# design.net
KiCad netlist of a schematic drawn in Altium Designer
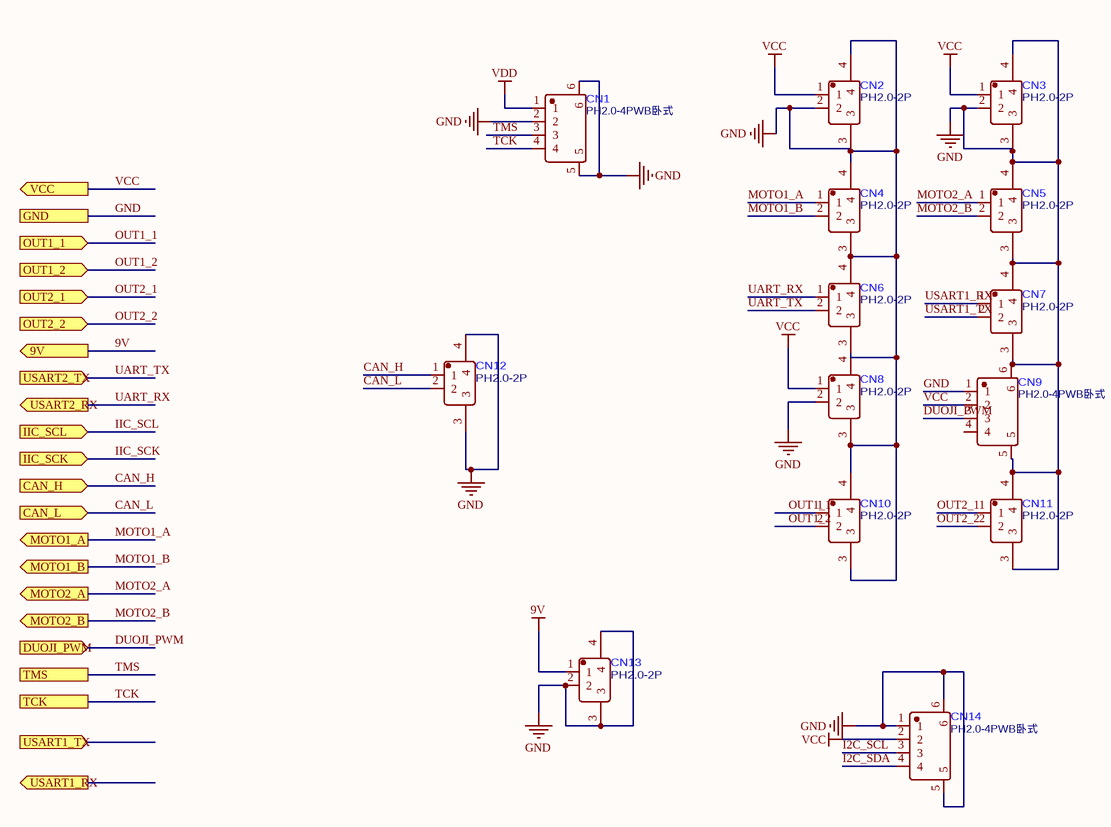
[diagram p0: 外围接口.SchDoc]

(export (version "E")
  (design (tool "Eeschema 10.0.6"))
  (components
    (comp (ref "CN1")
      (value "PH2.0-4PWB卧式")
      (footprint "CONN-SMD_PH2.0-4PWB")
      (libsource (lib "PH2.0-4PWB卧式_2021-08-21") (part "PH2.0-4PWB卧式"))
    )
    (comp (ref "CN2")
      (value "PH2.0-2P")
      (footprint "CONN-SMD_PH2.0-1X2PW")
      (libsource (lib "PH2.0-2P_2021-08-20") (part "PH2.0-2P"))
    )
    (comp (ref "CN3")
      (value "PH2.0-2P")
      (footprint "CONN-SMD_PH2.0-1X2PW")
      (libsource (lib "PH2.0-2P_2021-08-20") (part "PH2.0-2P"))
    )
    (comp (ref "CN4")
      (value "PH2.0-2P")
      (footprint "CONN-SMD_PH2.0-1X2PW")
      (libsource (lib "PH2.0-2P_2021-08-20") (part "PH2.0-2P"))
    )
    (comp (ref "CN5")
      (value "PH2.0-2P")
      (footprint "CONN-SMD_PH2.0-1X2PW")
      (libsource (lib "PH2.0-2P_2021-08-20") (part "PH2.0-2P"))
    )
    (comp (ref "CN6")
      (value "PH2.0-2P")
      (footprint "CONN-SMD_PH2.0-1X2PW")
      (libsource (lib "PH2.0-2P_2021-08-20") (part "PH2.0-2P"))
    )
    (comp (ref "CN7")
      (value "PH2.0-2P")
      (footprint "CONN-SMD_PH2.0-1X2PW")
      (libsource (lib "PH2.0-2P_2021-08-20") (part "PH2.0-2P"))
    )
    (comp (ref "CN8")
      (value "PH2.0-2P")
      (footprint "CONN-SMD_PH2.0-1X2PW")
      (libsource (lib "PH2.0-2P_2021-08-20") (part "PH2.0-2P"))
    )
    (comp (ref "CN9")
      (value "PH2.0-4PWB卧式")
      (footprint "CONN-SMD_PH2.0-4PWB")
      (libsource (lib "PH2.0-4PWB卧式_2021-08-21") (part "PH2.0-4PWB卧式"))
    )
    (comp (ref "CN10")
      (value "PH2.0-2P")
      (footprint "CONN-SMD_PH2.0-1X2PW")
      (libsource (lib "PH2.0-2P_2021-08-20") (part "PH2.0-2P"))
    )
    (comp (ref "CN11")
      (value "PH2.0-2P")
      (footprint "CONN-SMD_PH2.0-1X2PW")
      (libsource (lib "PH2.0-2P_2021-08-20") (part "PH2.0-2P"))
    )
    (comp (ref "CN12")
      (value "PH2.0-2P")
      (footprint "CONN-SMD_PH2.0-1X2PW")
      (libsource (lib "PH2.0-2P_2021-08-20") (part "PH2.0-2P"))
    )
    (comp (ref "CN13")
      (value "PH2.0-2P")
      (footprint "CONN-SMD_PH2.0-1X2PW")
      (libsource (lib "PH2.0-2P_2021-08-20") (part "PH2.0-2P"))
    )
    (comp (ref "CN14")
      (value "PH2.0-4PWB卧式")
      (footprint "CONN-SMD_PH2.0-4PWB")
      (libsource (lib "PH2.0-4PWB卧式_2021-08-21") (part "PH2.0-4PWB卧式"))
    )
  )
  (nets
    (net (code "1") (name "/CAN_H") (class "Default")
      (node (ref "CN12") (pin "1") (pinfunction "1_1") (pintype "passive"))
    )
    (net (code "2") (name "/CAN_L") (class "Default")
      (node (ref "CN12") (pin "2") (pinfunction "2_2") (pintype "passive"))
    )
    (net (code "3") (name "/DUOJI_PWM") (class "Default")
      (node (ref "CN9") (pin "3") (pinfunction "3_3") (pintype "passive"))
    )
    (net (code "4") (name "/I2C_SCL") (class "Default")
      (node (ref "CN14") (pin "3") (pinfunction "3_3") (pintype "passive"))
    )
    (net (code "5") (name "/I2C_SDA") (class "Default")
      (node (ref "CN14") (pin "4") (pinfunction "4_4") (pintype "passive"))
    )
    (net (code "8") (name "/MOTO1_A") (class "Default")
      (node (ref "CN4") (pin "1") (pinfunction "1_1") (pintype "passive"))
    )
    (net (code "9") (name "/MOTO1_B") (class "Default")
      (node (ref "CN4") (pin "2") (pinfunction "2_2") (pintype "passive"))
    )
    (net (code "10") (name "/MOTO2_A") (class "Default")
      (node (ref "CN5") (pin "1") (pinfunction "1_1") (pintype "passive"))
    )
    (net (code "11") (name "/MOTO2_B") (class "Default")
      (node (ref "CN5") (pin "2") (pinfunction "2_2") (pintype "passive"))
    )
    (net (code "12") (name "/OUT1_1") (class "Default")
      (node (ref "CN10") (pin "1") (pinfunction "1_1") (pintype "passive"))
    )
    (net (code "13") (name "/OUT1_2") (class "Default")
      (node (ref "CN10") (pin "2") (pinfunction "2_2") (pintype "passive"))
    )
    (net (code "14") (name "/OUT2_1") (class "Default")
      (node (ref "CN11") (pin "1") (pinfunction "1_1") (pintype "passive"))
    )
    (net (code "15") (name "/OUT2_2") (class "Default")
      (node (ref "CN11") (pin "2") (pinfunction "2_2") (pintype "passive"))
    )
    (net (code "16") (name "/TCK") (class "Default")
      (node (ref "CN1") (pin "4") (pinfunction "4_4") (pintype "passive"))
    )
    (net (code "17") (name "/TMS") (class "Default")
      (node (ref "CN1") (pin "3") (pinfunction "3_3") (pintype "passive"))
    )
    (net (code "18") (name "/UART_RX") (class "Default")
      (node (ref "CN6") (pin "1") (pinfunction "1_1") (pintype "passive"))
    )
    (net (code "19") (name "/UART_TX") (class "Default")
      (node (ref "CN6") (pin "2") (pinfunction "2_2") (pintype "passive"))
    )
    (net (code "20") (name "/USART1_RX") (class "Default")
      (node (ref "CN7") (pin "1") (pinfunction "1_1") (pintype "passive"))
    )
    (net (code "21") (name "/USART1_TX") (class "Default")
      (node (ref "CN7") (pin "2") (pinfunction "2_2") (pintype "passive"))
    )
    (net (code "22") (name "9V") (class "Default")
      (node (ref "CN13") (pin "1") (pinfunction "1_1") (pintype "passive"))
    )
    (net (code "23") (name "GND") (class "Default")
      (node (ref "CN1") (pin "2") (pinfunction "2_2") (pintype "passive"))
      (node (ref "CN1") (pin "5") (pinfunction "5_5") (pintype "passive"))
      (node (ref "CN1") (pin "6") (pinfunction "6_6") (pintype "passive"))
      (node (ref "CN10") (pin "3") (pinfunction "3_3") (pintype "passive"))
      (node (ref "CN10") (pin "4") (pinfunction "4_4") (pintype "passive"))
      (node (ref "CN11") (pin "3") (pinfunction "3_3") (pintype "passive"))
      (node (ref "CN11") (pin "4") (pinfunction "4_4") (pintype "passive"))
      (node (ref "CN12") (pin "3") (pinfunction "3_3") (pintype "passive"))
      (node (ref "CN12") (pin "4") (pinfunction "4_4") (pintype "passive"))
      (node (ref "CN13") (pin "2") (pinfunction "2_2") (pintype "passive"))
      (node (ref "CN13") (pin "3") (pinfunction "3_3") (pintype "passive"))
      (node (ref "CN13") (pin "4") (pinfunction "4_4") (pintype "passive"))
      (node (ref "CN14") (pin "1") (pinfunction "1_1") (pintype "passive"))
      (node (ref "CN14") (pin "5") (pinfunction "5_5") (pintype "passive"))
      (node (ref "CN14") (pin "6") (pinfunction "6_6") (pintype "passive"))
      (node (ref "CN2") (pin "2") (pinfunction "2_2") (pintype "passive"))
      (node (ref "CN2") (pin "3") (pinfunction "3_3") (pintype "passive"))
      (node (ref "CN2") (pin "4") (pinfunction "4_4") (pintype "passive"))
      (node (ref "CN3") (pin "2") (pinfunction "2_2") (pintype "passive"))
      (node (ref "CN3") (pin "3") (pinfunction "3_3") (pintype "passive"))
      (node (ref "CN3") (pin "4") (pinfunction "4_4") (pintype "passive"))
      (node (ref "CN4") (pin "3") (pinfunction "3_3") (pintype "passive"))
      (node (ref "CN4") (pin "4") (pinfunction "4_4") (pintype "passive"))
      (node (ref "CN5") (pin "3") (pinfunction "3_3") (pintype "passive"))
      (node (ref "CN5") (pin "4") (pinfunction "4_4") (pintype "passive"))
      (node (ref "CN6") (pin "3") (pinfunction "3_3") (pintype "passive"))
      (node (ref "CN6") (pin "4") (pinfunction "4_4") (pintype "passive"))
      (node (ref "CN7") (pin "3") (pinfunction "3_3") (pintype "passive"))
      (node (ref "CN7") (pin "4") (pinfunction "4_4") (pintype "passive"))
      (node (ref "CN8") (pin "2") (pinfunction "2_2") (pintype "passive"))
      (node (ref "CN8") (pin "3") (pinfunction "3_3") (pintype "passive"))
      (node (ref "CN9") (pin "1") (pinfunction "1_1") (pintype "passive"))
      (node (ref "CN9") (pin "5") (pinfunction "5_5") (pintype "passive"))
      (node (ref "CN9") (pin "6") (pinfunction "6_6") (pintype "passive"))
    )
    (net (code "24") (name "VCC") (class "Default")
      (node (ref "CN14") (pin "2") (pinfunction "2_2") (pintype "passive"))
      (node (ref "CN2") (pin "1") (pinfunction "1_1") (pintype "passive"))
      (node (ref "CN3") (pin "1") (pinfunction "1_1") (pintype "passive"))
      (node (ref "CN8") (pin "1") (pinfunction "1_1") (pintype "passive"))
      (node (ref "CN9") (pin "2") (pinfunction "2_2") (pintype "passive"))
    )
    (net (code "25") (name "VDD") (class "Default")
      (node (ref "CN1") (pin "1") (pinfunction "1_1") (pintype "passive"))
    )
    (net (code "26") (name "unconnected-(CN8-Pad4)") (class "Default")
      (node (ref "CN8") (pin "4") (pinfunction "4_4") (pintype "passive"))
    )
    (net (code "27") (name "unconnected-(CN9-Pad4)") (class "Default")
      (node (ref "CN9") (pin "4") (pinfunction "4_4") (pintype "passive"))
    )
  )
)
